# Antennae0_1.net
KiCad netlist of a schematic drawn in EAGLE
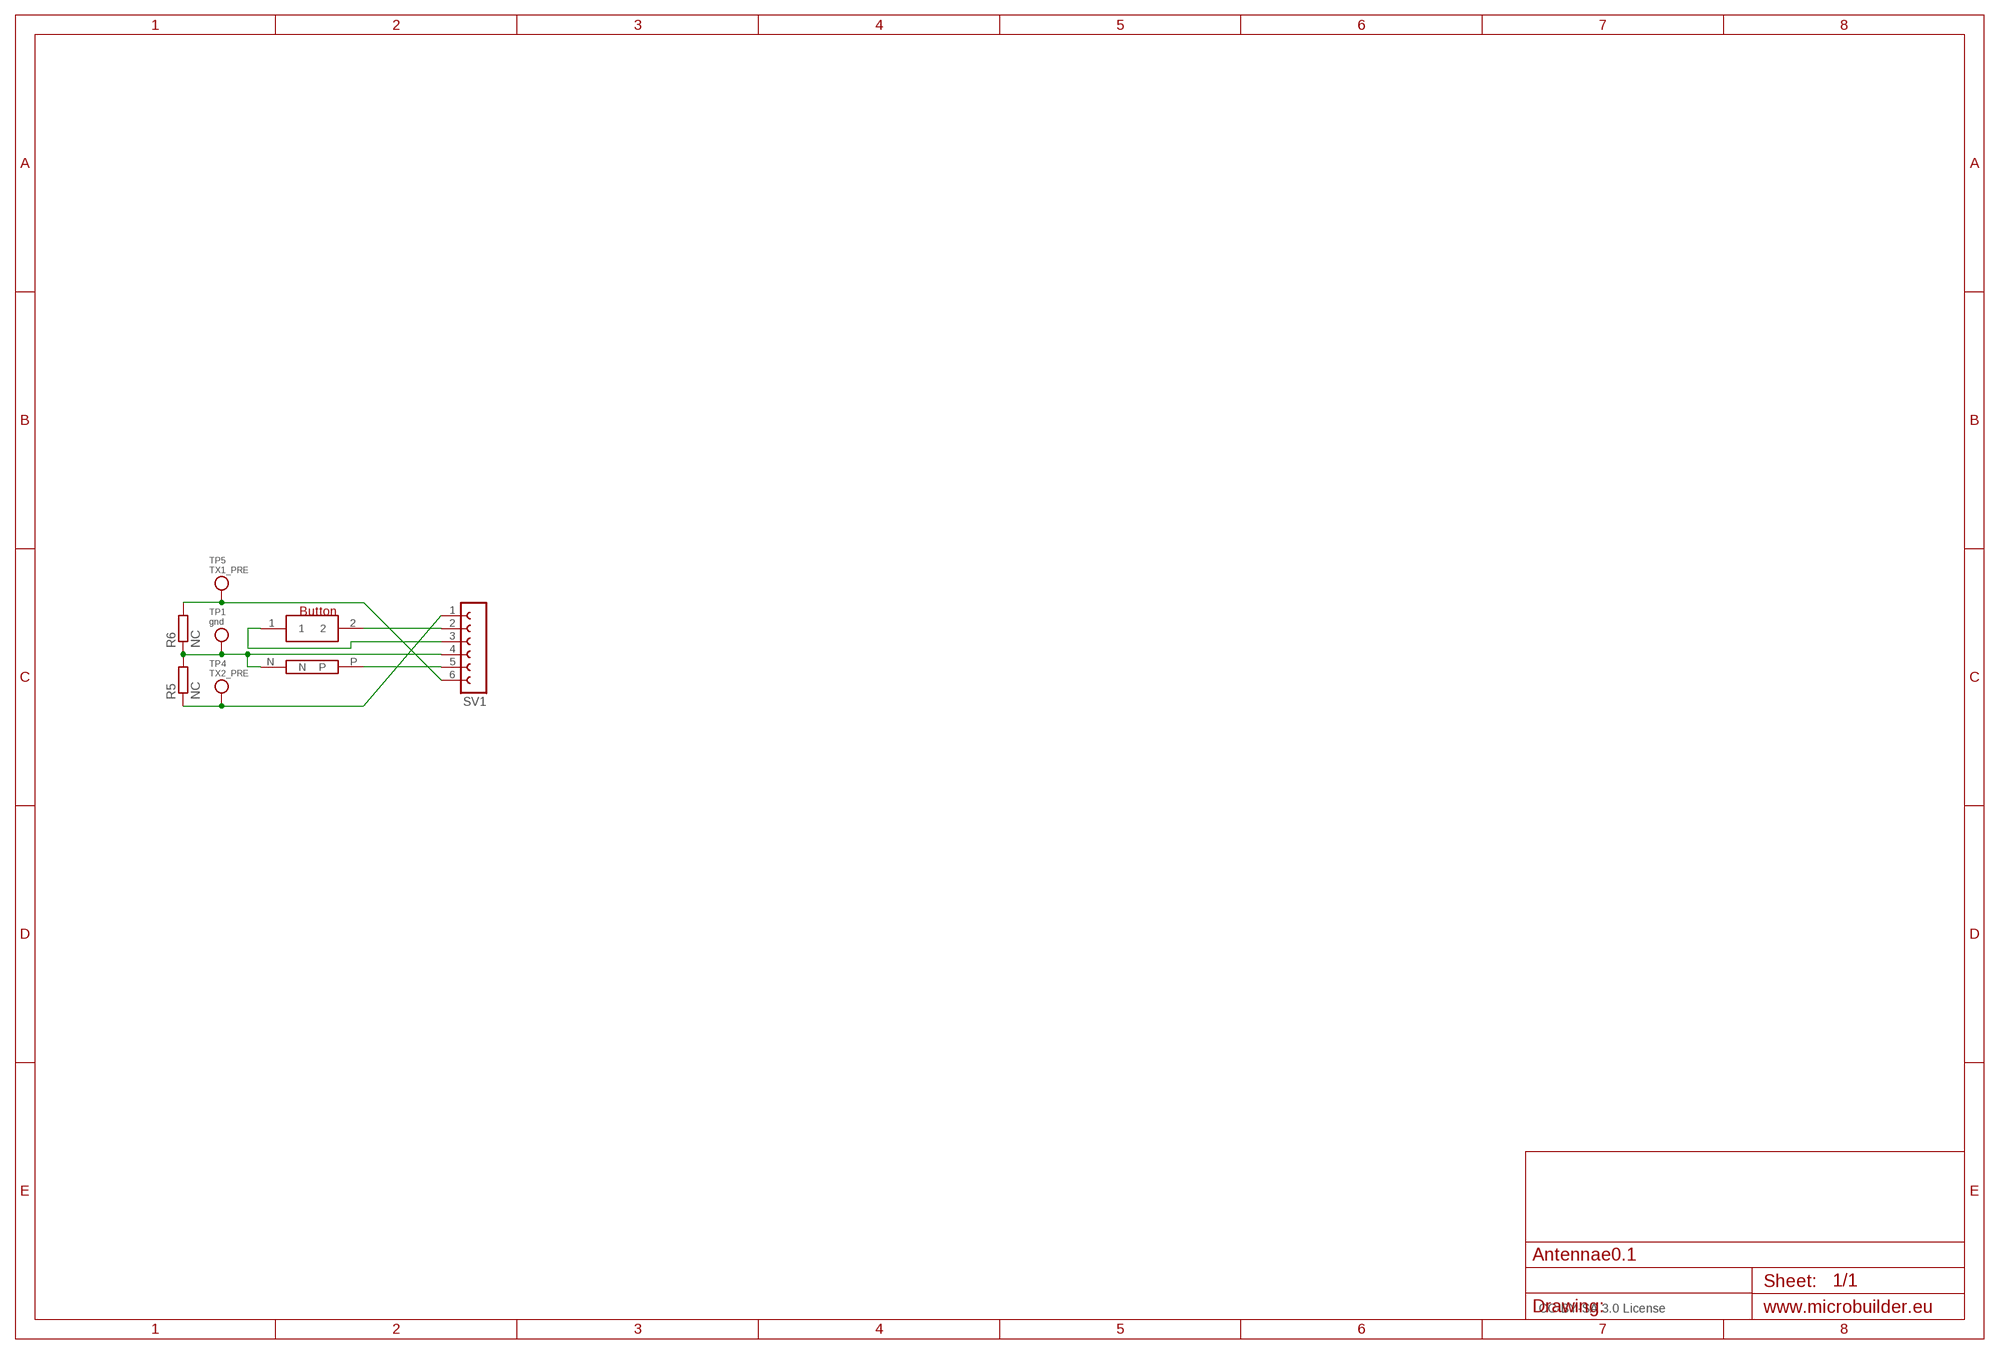
[diagram p0: schematic, sheet 1]

(export (version "E")
  (design (tool "Eeschema 10.0.6"))
  (components
    (comp (ref "R5")
      (value "NC")
      (footprint "eagle-import:R0201")
      (libsource (lib "eagle-import") (part "R-EU_R0201"))
    )
    (comp (ref "R6")
      (value "NC")
      (footprint "eagle-import:R0201")
      (libsource (lib "eagle-import") (part "R-EU_R0201"))
    )
    (comp (ref "SV1")
      (value "FE06-1")
      (footprint "eagle-import:FE06")
      (libsource (lib "eagle-import") (part "FE06-1"))
    )
    (comp (ref "TP1")
      (value "gnd")
      (footprint "eagle-import:TESTPOINT_PAD_2MM")
      (libsource (lib "eagle-import") (part "TESTPOINTPAD"))
    )
    (comp (ref "TP4")
      (value "TX2_PRE")
      (footprint "eagle-import:TESTPOINT_PAD_2MM")
      (libsource (lib "eagle-import") (part "TESTPOINTPAD"))
    )
    (comp (ref "TP5")
      (value "TX1_PRE")
      (footprint "eagle-import:TESTPOINT_PAD_2MM")
      (libsource (lib "eagle-import") (part "TESTPOINTPAD"))
    )
    (comp (ref "U$1")
      (value "BUTTON")
      (footprint "eagle-import:BUTTON")
      (libsource (lib "eagle-import") (part "BUTTON"))
    )
    (comp (ref "U$2")
      (value "LED(805)")
      (footprint "eagle-import:LED(805)")
      (libsource (lib "eagle-import") (part "LED(805)"))
    )
  )
  (nets
    (net (code "1") (name "Net-(R5-Pad1)") (class "Default")
      (node (ref "R5") (pin "1") (pinfunction "1_1") (pintype "passive"))
      (node (ref "SV1") (pin "1") (pinfunction "1_1") (pintype "passive"))
      (node (ref "TP4") (pin "P$1") (pinfunction "P$1_P$1") (pintype "bidirectional"))
    )
    (net (code "2") (name "Net-(R5-Pad2)") (class "Default")
      (node (ref "R5") (pin "2") (pinfunction "2_2") (pintype "passive"))
      (node (ref "R6") (pin "1") (pinfunction "1_1") (pintype "passive"))
      (node (ref "SV1") (pin "4") (pinfunction "4_4") (pintype "passive"))
      (node (ref "TP1") (pin "P$1") (pinfunction "P$1_P$1") (pintype "bidirectional"))
      (node (ref "U$2") (pin "N") (pinfunction "N_N") (pintype "bidirectional"))
    )
    (net (code "3") (name "Net-(R6-Pad2)") (class "Default")
      (node (ref "R6") (pin "2") (pinfunction "2_2") (pintype "passive"))
      (node (ref "SV1") (pin "6") (pinfunction "6_6") (pintype "passive"))
      (node (ref "TP5") (pin "P$1") (pinfunction "P$1_P$1") (pintype "bidirectional"))
    )
    (net (code "4") (name "Net-(SV1-Pad2)") (class "Default")
      (node (ref "SV1") (pin "2") (pinfunction "2_2") (pintype "passive"))
      (node (ref "U$1") (pin "2") (pinfunction "2_2") (pintype "bidirectional"))
    )
    (net (code "5") (name "Net-(SV1-Pad3)") (class "Default")
      (node (ref "SV1") (pin "3") (pinfunction "3_3") (pintype "passive"))
      (node (ref "U$1") (pin "1") (pinfunction "1_1") (pintype "bidirectional"))
    )
    (net (code "6") (name "Net-(SV1-Pad5)") (class "Default")
      (node (ref "SV1") (pin "5") (pinfunction "5_5") (pintype "passive"))
      (node (ref "U$2") (pin "P") (pinfunction "P_P") (pintype "bidirectional"))
    )
  )
)
